# STRWHL-S07-V00-EncoderInput.net
KiCad netlist of a schematic drawn in Altium Designer
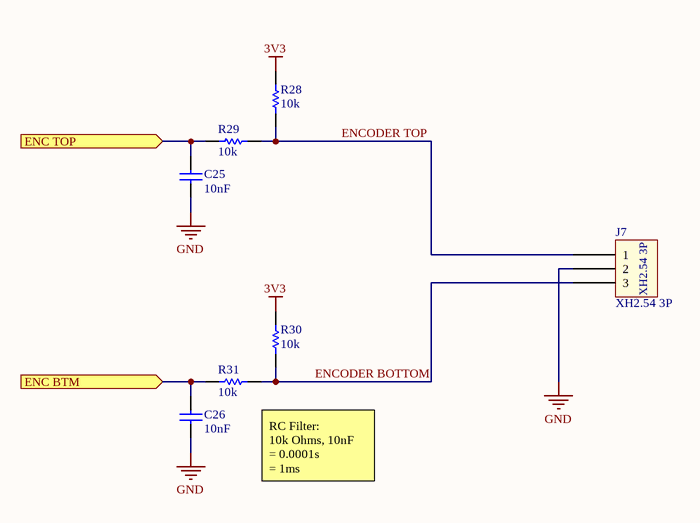
[diagram p0: STRWHL-S07-V00-EncoderInput.SchDoc]

(export (version "E")
  (design (tool "Eeschema 10.0.6"))
  (components
    (comp (ref "C25")
      (value "10nF")
      (footprint "Cap_Ceramic_0603")
      (description "Capacitor, Ceramic, SMD, 10nF, 50V, 5%, X7R, 0603")
      (libsource (lib "StandardCapacitors") (part "10nF 50V 5% X7R 0603"))
    )
    (comp (ref "C26")
      (value "10nF")
      (footprint "Cap_Ceramic_0603")
      (description "Capacitor, Ceramic, SMD, 10nF, 50V, 5%, X7R, 0603")
      (libsource (lib "StandardCapacitors") (part "10nF 50V 5% X7R 0603"))
    )
    (comp (ref "J7")
      (value "XH2.54 3P")
      (footprint "JST_XH254_3P_TH_RH")
      (libsource (lib "JST_XH254") (part "XH2.54 3P"))
    )
    (comp (ref "R28")
      (value "10k")
      (footprint "Res_ThinFilm_0603")
      (description "Resistor, SMD, 10k, 0.1W, 5%, 0603")
      (libsource (lib "StandardResistors") (part "10k 5% 0603"))
    )
    (comp (ref "R29")
      (value "10k")
      (footprint "Res_ThinFilm_0603")
      (description "Resistor, SMD, 10k, 0.1W, 5%, 0603")
      (libsource (lib "StandardResistors") (part "10k 5% 0603"))
    )
    (comp (ref "R30")
      (value "10k")
      (footprint "Res_ThinFilm_0603")
      (description "Resistor, SMD, 10k, 0.1W, 5%, 0603")
      (libsource (lib "StandardResistors") (part "10k 5% 0603"))
    )
    (comp (ref "R31")
      (value "10k")
      (footprint "Res_ThinFilm_0603")
      (description "Resistor, SMD, 10k, 0.1W, 5%, 0603")
      (libsource (lib "StandardResistors") (part "10k 5% 0603"))
    )
  )
  (nets
    (net (code "1") (name "/ENC BTM") (class "Default")
      (node (ref "C26") (pin "2") (pinfunction "2_2") (pintype "passive"))
      (node (ref "R31") (pin "2") (pinfunction "2_2") (pintype "passive"))
    )
    (net (code "2") (name "/ENC TOP") (class "Default")
      (node (ref "C25") (pin "2") (pinfunction "2_2") (pintype "passive"))
      (node (ref "R29") (pin "1") (pinfunction "1_1") (pintype "passive"))
    )
    (net (code "3") (name "/ENCODER BOTTOM") (class "Default")
      (node (ref "J7") (pin "3") (pinfunction "3_3") (pintype "passive"))
      (node (ref "R30") (pin "1") (pinfunction "1_1") (pintype "passive"))
      (node (ref "R31") (pin "1") (pinfunction "1_1") (pintype "passive"))
    )
    (net (code "4") (name "/ENCODER TOP") (class "Default")
      (node (ref "J7") (pin "1") (pinfunction "1_1") (pintype "passive"))
      (node (ref "R28") (pin "1") (pinfunction "1_1") (pintype "passive"))
      (node (ref "R29") (pin "2") (pinfunction "2_2") (pintype "passive"))
    )
    (net (code "5") (name "3V3") (class "Default")
      (node (ref "R28") (pin "2") (pinfunction "2_2") (pintype "passive"))
      (node (ref "R30") (pin "2") (pinfunction "2_2") (pintype "passive"))
    )
    (net (code "6") (name "GND") (class "Default")
      (node (ref "C25") (pin "1") (pinfunction "1_1") (pintype "passive"))
      (node (ref "C26") (pin "1") (pinfunction "1_1") (pintype "passive"))
      (node (ref "J7") (pin "2") (pinfunction "2_2") (pintype "passive"))
    )
  )
)
